# Adafruit_HaD_Proto_HAT_rev_A.net
KiCad netlist of a schematic drawn in EAGLE
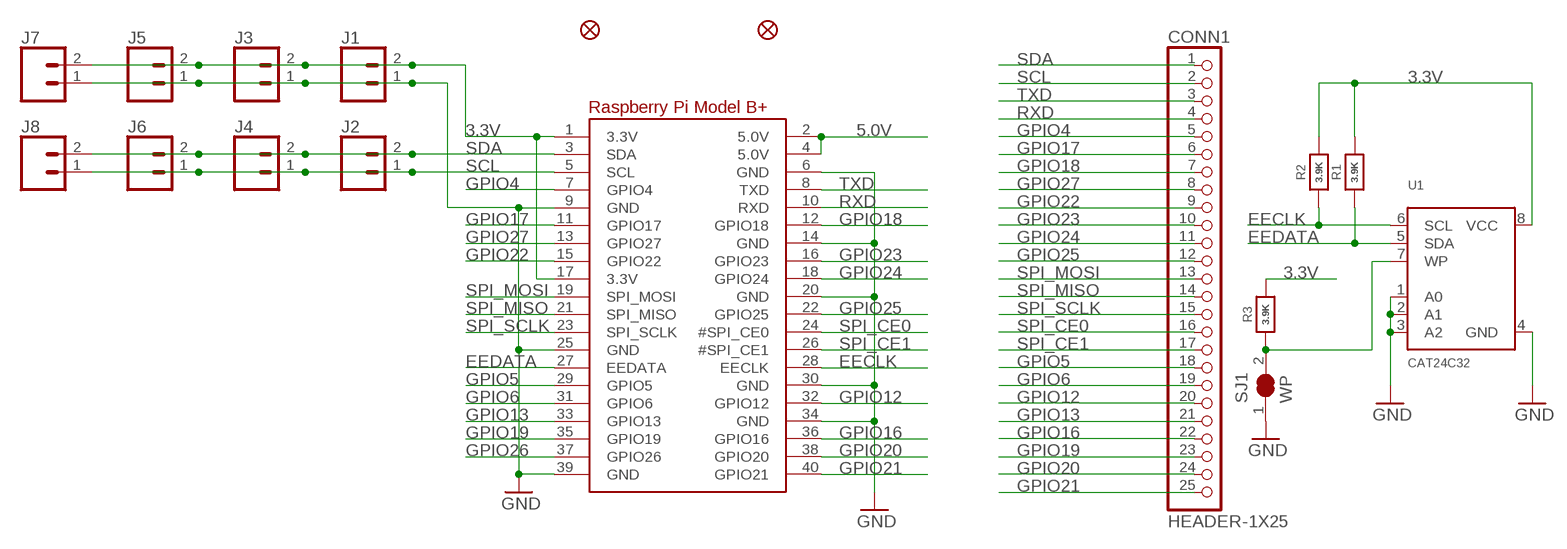
[diagram p0: schematic, sheet 1]

(export (version "E")
  (design (tool "Eeschema 10.0.6"))
  (components
    (comp (ref "CONN1")
      (value "HEADER-1X25")
      (footprint "eagle-import:1X25_ROUND_70MIL")
      (libsource (lib "eagle-import") (part "HEADER-1X25"))
    )
    (comp (ref "FID2")
      (value "FIDUCIAL\"\"")
      (footprint "eagle-import:FIDUCIAL_1MM")
      (libsource (lib "eagle-import") (part "FIDUCIAL{dblquote}{dblquote}"))
    )
    (comp (ref "FID3")
      (value "FIDUCIAL\"\"")
      (footprint "eagle-import:FIDUCIAL_1MM")
      (libsource (lib "eagle-import") (part "FIDUCIAL{dblquote}{dblquote}"))
    )
    (comp (ref "J1")
      (value "CONN_02LOCK")
      (footprint "eagle-import:1X02_LOCK")
      (libsource (lib "eagle-import") (part "CONN_02LOCK"))
    )
    (comp (ref "J2")
      (value "CONN_02LOCK")
      (footprint "eagle-import:1X02_LOCK")
      (libsource (lib "eagle-import") (part "CONN_02LOCK"))
    )
    (comp (ref "J3")
      (value "CONN_02LOCK")
      (footprint "eagle-import:1X02_LOCK")
      (libsource (lib "eagle-import") (part "CONN_02LOCK"))
    )
    (comp (ref "J4")
      (value "CONN_02LOCK")
      (footprint "eagle-import:1X02_LOCK")
      (libsource (lib "eagle-import") (part "CONN_02LOCK"))
    )
    (comp (ref "J5")
      (value "CONN_02LOCK")
      (footprint "eagle-import:1X02_LOCK")
      (libsource (lib "eagle-import") (part "CONN_02LOCK"))
    )
    (comp (ref "J6")
      (value "CONN_02LOCK")
      (footprint "eagle-import:1X02_LOCK")
      (libsource (lib "eagle-import") (part "CONN_02LOCK"))
    )
    (comp (ref "J7")
      (value "CONN_02LOCK")
      (footprint "eagle-import:1X02_LOCK")
      (libsource (lib "eagle-import") (part "CONN_02LOCK"))
    )
    (comp (ref "J8")
      (value "CONN_02LOCK")
      (footprint "eagle-import:1X02_LOCK")
      (libsource (lib "eagle-import") (part "CONN_02LOCK"))
    )
    (comp (ref "R1")
      (value "3.9K")
      (footprint "eagle-import:0805-NO")
      (libsource (lib "eagle-import") (part "RESISTOR0805_NOOUTLINE"))
    )
    (comp (ref "R2")
      (value "3.9K")
      (footprint "eagle-import:0805-NO")
      (libsource (lib "eagle-import") (part "RESISTOR0805_NOOUTLINE"))
    )
    (comp (ref "R3")
      (value "3.9K")
      (footprint "eagle-import:0805-NO")
      (libsource (lib "eagle-import") (part "RESISTOR0805_NOOUTLINE"))
    )
    (comp (ref "RPI1")
      (value "RASPBERRYPI_BPLUS_HATNOSLOTS")
      (footprint "eagle-import:PI_HAT_NOSLOTS")
      (libsource (lib "eagle-import") (part "RASPBERRYPI_BPLUS_HATNOSLOTS"))
    )
    (comp (ref "SJ1")
      (value "WP")
      (footprint "eagle-import:SOLDERJUMPER_CLOSEDWIRE")
      (libsource (lib "eagle-import") (part "SOLDERJUMPER_CLOSED"))
    )
    (comp (ref "U1")
      (value "CAT24C32")
      (footprint "eagle-import:SOIC8_150MIL")
      (libsource (lib "eagle-import") (part "EEPROM_I2C_SOIC8_GENERIC"))
    )
  )
  (nets
    (net (code "1") (name "/3.3V") (class "Default")
      (node (ref "J1") (pin "2") (pinfunction "2_2") (pintype "passive"))
      (node (ref "J3") (pin "2") (pinfunction "2_2") (pintype "passive"))
      (node (ref "J5") (pin "2") (pinfunction "2_2") (pintype "passive"))
      (node (ref "J7") (pin "2") (pinfunction "2_2") (pintype "passive"))
      (node (ref "R1") (pin "2") (pinfunction "2_2") (pintype "passive"))
      (node (ref "R2") (pin "2") (pinfunction "2_2") (pintype "passive"))
      (node (ref "R3") (pin "2") (pinfunction "2_2") (pintype "passive"))
      (node (ref "RPI1") (pin "1") (pinfunction "3.3V_1") (pintype "power_in"))
      (node (ref "RPI1") (pin "17") (pinfunction "3.3V_17") (pintype "power_in"))
      (node (ref "U1") (pin "8") (pinfunction "VCC_8") (pintype "power_in"))
    )
    (net (code "2") (name "/5.0V") (class "Default")
      (node (ref "RPI1") (pin "2") (pinfunction "5.0V_2") (pintype "power_in"))
      (node (ref "RPI1") (pin "4") (pinfunction "5.0V_4") (pintype "power_in"))
    )
    (net (code "3") (name "/EECLK") (class "Default")
      (node (ref "R2") (pin "1") (pinfunction "1_1") (pintype "passive"))
      (node (ref "RPI1") (pin "28") (pinfunction "EECLK_28") (pintype "power_in"))
      (node (ref "U1") (pin "6") (pinfunction "SCL_6") (pintype "input"))
    )
    (net (code "4") (name "/EEDATA") (class "Default")
      (node (ref "R1") (pin "1") (pinfunction "1_1") (pintype "passive"))
      (node (ref "RPI1") (pin "27") (pinfunction "EEDATA_27") (pintype "bidirectional"))
      (node (ref "U1") (pin "5") (pinfunction "SDA_5") (pintype "bidirectional"))
    )
    (net (code "5") (name "/GPIO4") (class "Default")
      (node (ref "CONN1") (pin "5") (pinfunction "5_5") (pintype "passive"))
      (node (ref "RPI1") (pin "7") (pinfunction "GPIO4_7") (pintype "bidirectional"))
    )
    (net (code "6") (name "/GPIO5") (class "Default")
      (node (ref "CONN1") (pin "18") (pinfunction "18_18") (pintype "passive"))
      (node (ref "RPI1") (pin "29") (pinfunction "GPIO5_29") (pintype "bidirectional"))
    )
    (net (code "7") (name "/GPIO6") (class "Default")
      (node (ref "CONN1") (pin "19") (pinfunction "19_19") (pintype "passive"))
      (node (ref "RPI1") (pin "31") (pinfunction "GPIO6_31") (pintype "power_in"))
    )
    (net (code "8") (name "/GPIO12") (class "Default")
      (node (ref "CONN1") (pin "20") (pinfunction "20_20") (pintype "passive"))
      (node (ref "RPI1") (pin "32") (pinfunction "GPIO12_32") (pintype "bidirectional"))
    )
    (net (code "9") (name "/GPIO13") (class "Default")
      (node (ref "CONN1") (pin "21") (pinfunction "21_21") (pintype "passive"))
      (node (ref "RPI1") (pin "33") (pinfunction "GPIO13_33") (pintype "bidirectional"))
    )
    (net (code "10") (name "/GPIO16") (class "Default")
      (node (ref "CONN1") (pin "22") (pinfunction "22_22") (pintype "passive"))
      (node (ref "RPI1") (pin "36") (pinfunction "GPIO16_36") (pintype "power_in"))
    )
    (net (code "11") (name "/GPIO17") (class "Default")
      (node (ref "CONN1") (pin "6") (pinfunction "6_6") (pintype "passive"))
      (node (ref "RPI1") (pin "11") (pinfunction "GPIO17_11") (pintype "bidirectional"))
    )
    (net (code "12") (name "/GPIO18") (class "Default")
      (node (ref "CONN1") (pin "7") (pinfunction "7_7") (pintype "passive"))
      (node (ref "RPI1") (pin "12") (pinfunction "GPIO18_12") (pintype "bidirectional"))
    )
    (net (code "13") (name "/GPIO19") (class "Default")
      (node (ref "CONN1") (pin "23") (pinfunction "23_23") (pintype "passive"))
      (node (ref "RPI1") (pin "35") (pinfunction "GPIO19_35") (pintype "bidirectional"))
    )
    (net (code "14") (name "/GPIO20") (class "Default")
      (node (ref "CONN1") (pin "24") (pinfunction "24_24") (pintype "passive"))
      (node (ref "RPI1") (pin "38") (pinfunction "GPIO20_38") (pintype "bidirectional"))
    )
    (net (code "15") (name "/GPIO21") (class "Default")
      (node (ref "CONN1") (pin "25") (pinfunction "25_25") (pintype "passive"))
      (node (ref "RPI1") (pin "40") (pinfunction "GPIO21_40") (pintype "bidirectional"))
    )
    (net (code "16") (name "/GPIO22") (class "Default")
      (node (ref "CONN1") (pin "9") (pinfunction "9_9") (pintype "passive"))
      (node (ref "RPI1") (pin "15") (pinfunction "GPIO22_15") (pintype "bidirectional"))
    )
    (net (code "17") (name "/GPIO23") (class "Default")
      (node (ref "CONN1") (pin "10") (pinfunction "10_10") (pintype "passive"))
      (node (ref "RPI1") (pin "16") (pinfunction "GPIO23_16") (pintype "bidirectional"))
    )
    (net (code "18") (name "/GPIO24") (class "Default")
      (node (ref "CONN1") (pin "11") (pinfunction "11_11") (pintype "passive"))
      (node (ref "RPI1") (pin "18") (pinfunction "GPIO24_18") (pintype "bidirectional"))
    )
    (net (code "19") (name "/GPIO25") (class "Default")
      (node (ref "CONN1") (pin "12") (pinfunction "12_12") (pintype "passive"))
      (node (ref "RPI1") (pin "22") (pinfunction "GPIO25_22") (pintype "bidirectional"))
    )
    (net (code "20") (name "/GPIO26") (class "Default")
      (node (ref "RPI1") (pin "37") (pinfunction "GPIO26_37") (pintype "bidirectional"))
    )
    (net (code "21") (name "/GPIO27") (class "Default")
      (node (ref "CONN1") (pin "8") (pinfunction "8_8") (pintype "passive"))
      (node (ref "RPI1") (pin "13") (pinfunction "GPIO27_13") (pintype "bidirectional"))
    )
    (net (code "22") (name "/RXD") (class "Default")
      (node (ref "CONN1") (pin "4") (pinfunction "4_4") (pintype "passive"))
      (node (ref "RPI1") (pin "10") (pinfunction "RXD_10") (pintype "bidirectional"))
    )
    (net (code "23") (name "/SCL") (class "Default")
      (node (ref "CONN1") (pin "2") (pinfunction "2_2") (pintype "passive"))
      (node (ref "J2") (pin "1") (pinfunction "1_1") (pintype "passive"))
      (node (ref "J4") (pin "1") (pinfunction "1_1") (pintype "passive"))
      (node (ref "J6") (pin "1") (pinfunction "1_1") (pintype "passive"))
      (node (ref "J8") (pin "1") (pinfunction "1_1") (pintype "passive"))
      (node (ref "RPI1") (pin "5") (pinfunction "SCL_5") (pintype "bidirectional"))
    )
    (net (code "24") (name "/SDA") (class "Default")
      (node (ref "CONN1") (pin "1") (pinfunction "1_1") (pintype "passive"))
      (node (ref "J2") (pin "2") (pinfunction "2_2") (pintype "passive"))
      (node (ref "J4") (pin "2") (pinfunction "2_2") (pintype "passive"))
      (node (ref "J6") (pin "2") (pinfunction "2_2") (pintype "passive"))
      (node (ref "J8") (pin "2") (pinfunction "2_2") (pintype "passive"))
      (node (ref "RPI1") (pin "3") (pinfunction "SDA_3") (pintype "bidirectional"))
    )
    (net (code "25") (name "/SPI_CE0") (class "Default")
      (node (ref "CONN1") (pin "16") (pinfunction "16_16") (pintype "passive"))
      (node (ref "RPI1") (pin "24") (pinfunction "#SPI_CE0_24") (pintype "bidirectional"))
    )
    (net (code "26") (name "/SPI_CE1") (class "Default")
      (node (ref "CONN1") (pin "17") (pinfunction "17_17") (pintype "passive"))
      (node (ref "RPI1") (pin "26") (pinfunction "#SPI_CE1_26") (pintype "bidirectional"))
    )
    (net (code "27") (name "/SPI_MISO") (class "Default")
      (node (ref "CONN1") (pin "14") (pinfunction "14_14") (pintype "passive"))
      (node (ref "RPI1") (pin "21") (pinfunction "SPI_MISO_21") (pintype "bidirectional"))
    )
    (net (code "28") (name "/SPI_MOSI") (class "Default")
      (node (ref "CONN1") (pin "13") (pinfunction "13_13") (pintype "passive"))
      (node (ref "RPI1") (pin "19") (pinfunction "SPI_MOSI_19") (pintype "bidirectional"))
    )
    (net (code "29") (name "/SPI_SCLK") (class "Default")
      (node (ref "CONN1") (pin "15") (pinfunction "15_15") (pintype "passive"))
      (node (ref "RPI1") (pin "23") (pinfunction "SPI_SCLK_23") (pintype "bidirectional"))
    )
    (net (code "30") (name "/TXD") (class "Default")
      (node (ref "CONN1") (pin "3") (pinfunction "3_3") (pintype "passive"))
      (node (ref "RPI1") (pin "8") (pinfunction "TXD_8") (pintype "output"))
    )
    (net (code "31") (name "GND") (class "Default")
      (node (ref "J1") (pin "1") (pinfunction "1_1") (pintype "passive"))
      (node (ref "J3") (pin "1") (pinfunction "1_1") (pintype "passive"))
      (node (ref "J5") (pin "1") (pinfunction "1_1") (pintype "passive"))
      (node (ref "J7") (pin "1") (pinfunction "1_1") (pintype "passive"))
      (node (ref "RPI1") (pin "14") (pinfunction "GND_14") (pintype "power_in"))
      (node (ref "RPI1") (pin "20") (pinfunction "GND_20") (pintype "power_in"))
      (node (ref "RPI1") (pin "25") (pinfunction "GND_25") (pintype "power_in"))
      (node (ref "RPI1") (pin "30") (pinfunction "GND_30") (pintype "bidirectional"))
      (node (ref "RPI1") (pin "34") (pinfunction "GND_34") (pintype "bidirectional"))
      (node (ref "RPI1") (pin "39") (pinfunction "GND_39") (pintype "power_in"))
      (node (ref "RPI1") (pin "6") (pinfunction "GND_6") (pintype "power_in"))
      (node (ref "RPI1") (pin "9") (pinfunction "GND_9") (pintype "power_in"))
      (node (ref "SJ1") (pin "1") (pinfunction "1_1") (pintype "passive"))
      (node (ref "U1") (pin "1") (pinfunction "A0_1") (pintype "input"))
      (node (ref "U1") (pin "2") (pinfunction "A1_2") (pintype "input"))
      (node (ref "U1") (pin "3") (pinfunction "A2_3") (pintype "input"))
      (node (ref "U1") (pin "4") (pinfunction "GND_4") (pintype "power_in"))
    )
    (net (code "32") (name "Net-(U1-WP)") (class "Default")
      (node (ref "R3") (pin "1") (pinfunction "1_1") (pintype "passive"))
      (node (ref "SJ1") (pin "2") (pinfunction "2_2") (pintype "passive"))
      (node (ref "U1") (pin "7") (pinfunction "WP_7") (pintype "input"))
    )
  )
)
